# rcal.net
KiCad netlist of a schematic drawn in EAGLE
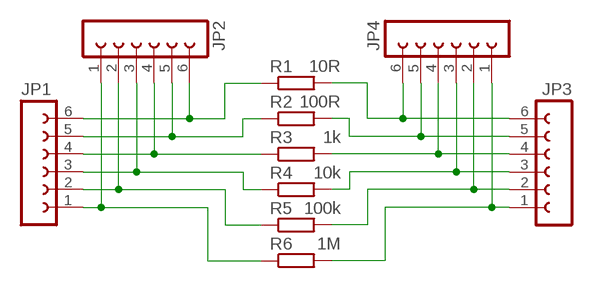
[diagram p0: schematic, sheet 1]

(export (version "E")
  (design (tool "Eeschema 10.0.6"))
  (components
    (comp (ref "JP1")
      (value "FE06-1")
      (footprint "eagle-import:FE06")
      (libsource (lib "eagle-import") (part "FE06-1"))
    )
    (comp (ref "JP2")
      (value "FE06-1")
      (footprint "eagle-import:FE06")
      (libsource (lib "eagle-import") (part "FE06-1"))
    )
    (comp (ref "JP3")
      (value "FE06-1")
      (footprint "eagle-import:FE06")
      (libsource (lib "eagle-import") (part "FE06-1"))
    )
    (comp (ref "JP4")
      (value "FE06-1")
      (footprint "eagle-import:FE06")
      (libsource (lib "eagle-import") (part "FE06-1"))
    )
    (comp (ref "R1")
      (value "10R")
      (footprint "eagle-import:R0805")
      (libsource (lib "eagle-import") (part "R-EU_R0805"))
    )
    (comp (ref "R2")
      (value "100R")
      (footprint "eagle-import:R0805")
      (libsource (lib "eagle-import") (part "R-EU_R0805"))
    )
    (comp (ref "R3")
      (value "1k")
      (footprint "eagle-import:R0805")
      (libsource (lib "eagle-import") (part "R-EU_R0805"))
    )
    (comp (ref "R4")
      (value "10k")
      (footprint "eagle-import:R0805")
      (libsource (lib "eagle-import") (part "R-EU_R0805"))
    )
    (comp (ref "R5")
      (value "100k")
      (footprint "eagle-import:R0805")
      (libsource (lib "eagle-import") (part "R-EU_R0805"))
    )
    (comp (ref "R6")
      (value "1M")
      (footprint "eagle-import:R0805")
      (libsource (lib "eagle-import") (part "R-EU_R0805"))
    )
  )
  (nets
    (net (code "1") (name "Net-(JP1-Pad1)") (class "Default")
      (node (ref "JP1") (pin "1") (pinfunction "1_1") (pintype "passive"))
      (node (ref "JP2") (pin "1") (pinfunction "1_1") (pintype "passive"))
      (node (ref "R6") (pin "1") (pinfunction "1_1") (pintype "passive"))
    )
    (net (code "2") (name "Net-(JP1-Pad2)") (class "Default")
      (node (ref "JP1") (pin "2") (pinfunction "2_2") (pintype "passive"))
      (node (ref "JP2") (pin "2") (pinfunction "2_2") (pintype "passive"))
      (node (ref "R5") (pin "1") (pinfunction "1_1") (pintype "passive"))
    )
    (net (code "3") (name "Net-(JP1-Pad3)") (class "Default")
      (node (ref "JP1") (pin "3") (pinfunction "3_3") (pintype "passive"))
      (node (ref "JP2") (pin "3") (pinfunction "3_3") (pintype "passive"))
      (node (ref "R4") (pin "1") (pinfunction "1_1") (pintype "passive"))
    )
    (net (code "4") (name "Net-(JP1-Pad4)") (class "Default")
      (node (ref "JP1") (pin "4") (pinfunction "4_4") (pintype "passive"))
      (node (ref "JP2") (pin "4") (pinfunction "4_4") (pintype "passive"))
      (node (ref "R3") (pin "1") (pinfunction "1_1") (pintype "passive"))
    )
    (net (code "5") (name "Net-(JP1-Pad5)") (class "Default")
      (node (ref "JP1") (pin "5") (pinfunction "5_5") (pintype "passive"))
      (node (ref "JP2") (pin "5") (pinfunction "5_5") (pintype "passive"))
      (node (ref "R2") (pin "1") (pinfunction "1_1") (pintype "passive"))
    )
    (net (code "6") (name "Net-(JP1-Pad6)") (class "Default")
      (node (ref "JP1") (pin "6") (pinfunction "6_6") (pintype "passive"))
      (node (ref "JP2") (pin "6") (pinfunction "6_6") (pintype "passive"))
      (node (ref "R1") (pin "1") (pinfunction "1_1") (pintype "passive"))
    )
    (net (code "7") (name "Net-(JP3-Pad1)") (class "Default")
      (node (ref "JP3") (pin "1") (pinfunction "1_1") (pintype "passive"))
      (node (ref "JP4") (pin "1") (pinfunction "1_1") (pintype "passive"))
      (node (ref "R6") (pin "2") (pinfunction "2_2") (pintype "passive"))
    )
    (net (code "8") (name "Net-(JP3-Pad2)") (class "Default")
      (node (ref "JP3") (pin "2") (pinfunction "2_2") (pintype "passive"))
      (node (ref "JP4") (pin "2") (pinfunction "2_2") (pintype "passive"))
      (node (ref "R5") (pin "2") (pinfunction "2_2") (pintype "passive"))
    )
    (net (code "9") (name "Net-(JP3-Pad3)") (class "Default")
      (node (ref "JP3") (pin "3") (pinfunction "3_3") (pintype "passive"))
      (node (ref "JP4") (pin "3") (pinfunction "3_3") (pintype "passive"))
      (node (ref "R4") (pin "2") (pinfunction "2_2") (pintype "passive"))
    )
    (net (code "10") (name "Net-(JP3-Pad4)") (class "Default")
      (node (ref "JP3") (pin "4") (pinfunction "4_4") (pintype "passive"))
      (node (ref "JP4") (pin "4") (pinfunction "4_4") (pintype "passive"))
      (node (ref "R3") (pin "2") (pinfunction "2_2") (pintype "passive"))
    )
    (net (code "11") (name "Net-(JP3-Pad5)") (class "Default")
      (node (ref "JP3") (pin "5") (pinfunction "5_5") (pintype "passive"))
      (node (ref "JP4") (pin "5") (pinfunction "5_5") (pintype "passive"))
      (node (ref "R2") (pin "2") (pinfunction "2_2") (pintype "passive"))
    )
    (net (code "12") (name "Net-(JP3-Pad6)") (class "Default")
      (node (ref "JP3") (pin "6") (pinfunction "6_6") (pintype "passive"))
      (node (ref "JP4") (pin "6") (pinfunction "6_6") (pintype "passive"))
      (node (ref "R1") (pin "2") (pinfunction "2_2") (pintype "passive"))
    )
  )
)
